# SCH_NSD-Card_2024-10-09.net
KiCad netlist of a schematic drawn in EasyEDA
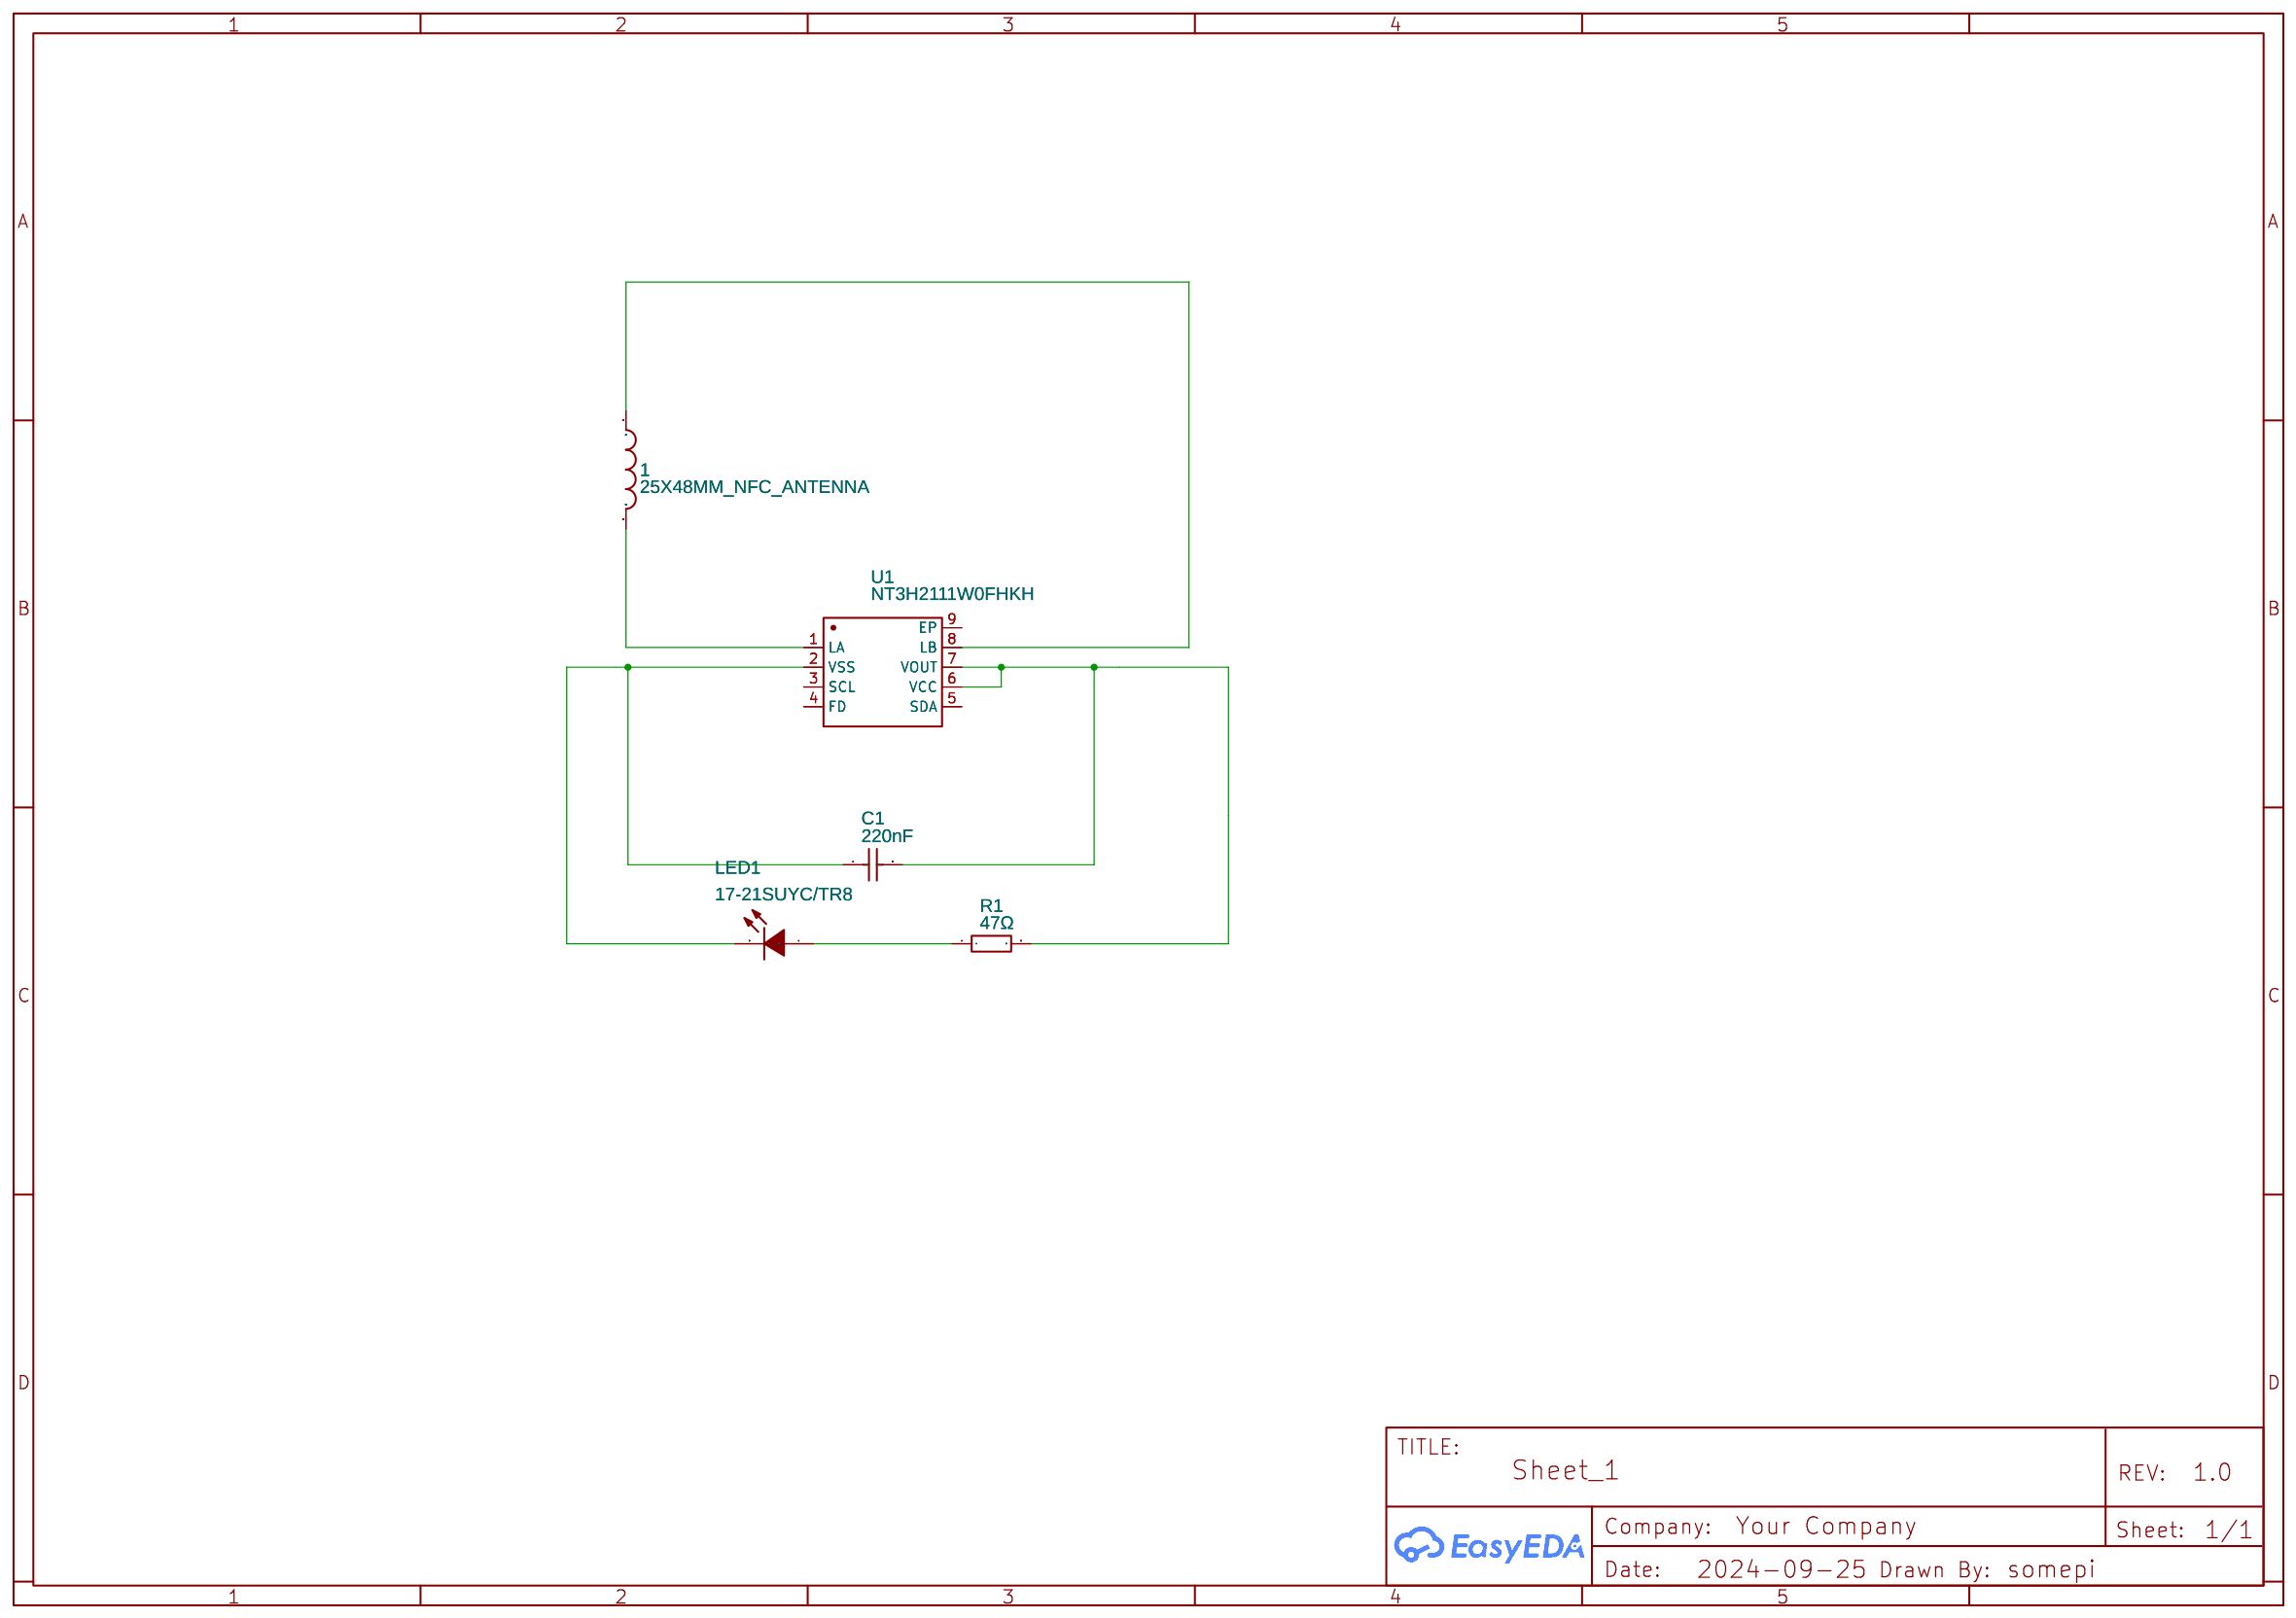
[diagram p0: schematic sheet]

(export (version "E")
  (design (tool "Eeschema 10.0.6"))
  (components
    (comp (ref "1") (value "25X48MM_NFC_ANTENNA") (libsource (lib "") (part "25X48MM_NFC_ANTENNA")))
    (comp (ref "C1")
      (value "220nF")
      (fields
        (field (name "Manufacturer Part") "CL10B224KA8NNNC")
        (field (name "Manufacturer") "SAMSUNG(三星)")
      )
      (libsource (lib "") (part "CL10B224KA8NNNC"))
    )
    (comp (ref "LED1")
      (value "17-21SUYC/TR8")
      (fields (field (name "Manufacturer Part") "KT-0805黄灯") (field (name "Manufacturer") "KENTO"))
      (libsource (lib "") (part "17-21SUYC/TR8"))
    )
    (comp (ref "R1")
      (value "47Ω")
      (fields
        (field (name "Manufacturer Part") "0603WAF470JT5E")
        (field (name "Manufacturer") "UNI-ROYAL(厚声)")
      )
      (libsource (lib "") (part "0603WAF470JT5E"))
    )
    (comp (ref "U1")
      (value "NT3H2111W0FHKH")
      (fields (field (name "Manufacturer") "NXP(恩智浦)"))
      (libsource (lib "") (part "NT3H2111W0FHKH"))
    )
  )
  (nets
    (net (code "1") (name "Net-(LED1-+)") (class "Default")
      (node (ref "LED1") (pin "1") (pinfunction "+_1") (pintype "unspecified"))
      (node (ref "R1") (pin "1") (pinfunction "1_1") (pintype "input"))
    )
    (net (code "2") (name "Net-(LED1--)") (class "Default")
      (node (ref "C1") (pin "1") (pinfunction "1_1") (pintype "input"))
      (node (ref "LED1") (pin "2") (pinfunction "-_2") (pintype "unspecified"))
      (node (ref "U1") (pin "2") (pinfunction "VSS_2") (pintype "unspecified"))
    )
    (net (code "3") (name "Net-(U1-LA)") (class "Default")
      (node (ref "1") (pin "P$2") (pinfunction "P$2_P$2") (pintype "bidirectional"))
      (node (ref "U1") (pin "1") (pinfunction "LA_1") (pintype "unspecified"))
    )
    (net (code "4") (name "Net-(U1-LB)") (class "Default")
      (node (ref "1") (pin "P$1") (pinfunction "P$1_P$1") (pintype "bidirectional"))
      (node (ref "U1") (pin "8") (pinfunction "LB_8") (pintype "unspecified"))
    )
    (net (code "5") (name "Net-(U1-VCC)") (class "Default")
      (node (ref "C1") (pin "2") (pinfunction "2_2") (pintype "input"))
      (node (ref "R1") (pin "2") (pinfunction "2_2") (pintype "input"))
      (node (ref "U1") (pin "6") (pinfunction "VCC_6") (pintype "unspecified"))
      (node (ref "U1") (pin "7") (pinfunction "VOUT_7") (pintype "unspecified"))
    )
    (net (code "6") (name "unconnected-(U1-EP-Pad9)") (class "Default")
      (node (ref "U1") (pin "9") (pinfunction "EP_9") (pintype "unspecified"))
    )
    (net (code "7") (name "unconnected-(U1-FD-Pad4)") (class "Default")
      (node (ref "U1") (pin "4") (pinfunction "FD_4") (pintype "unspecified"))
    )
    (net (code "8") (name "unconnected-(U1-SCL-Pad3)") (class "Default")
      (node (ref "U1") (pin "3") (pinfunction "SCL_3") (pintype "unspecified"))
    )
    (net (code "9") (name "unconnected-(U1-SDA-Pad5)") (class "Default")
      (node (ref "U1") (pin "5") (pinfunction "SDA_5") (pintype "unspecified"))
    )
  )
)
